# dental-unit-button_v1_0.net
KiCad netlist of a schematic drawn in Altium Designer
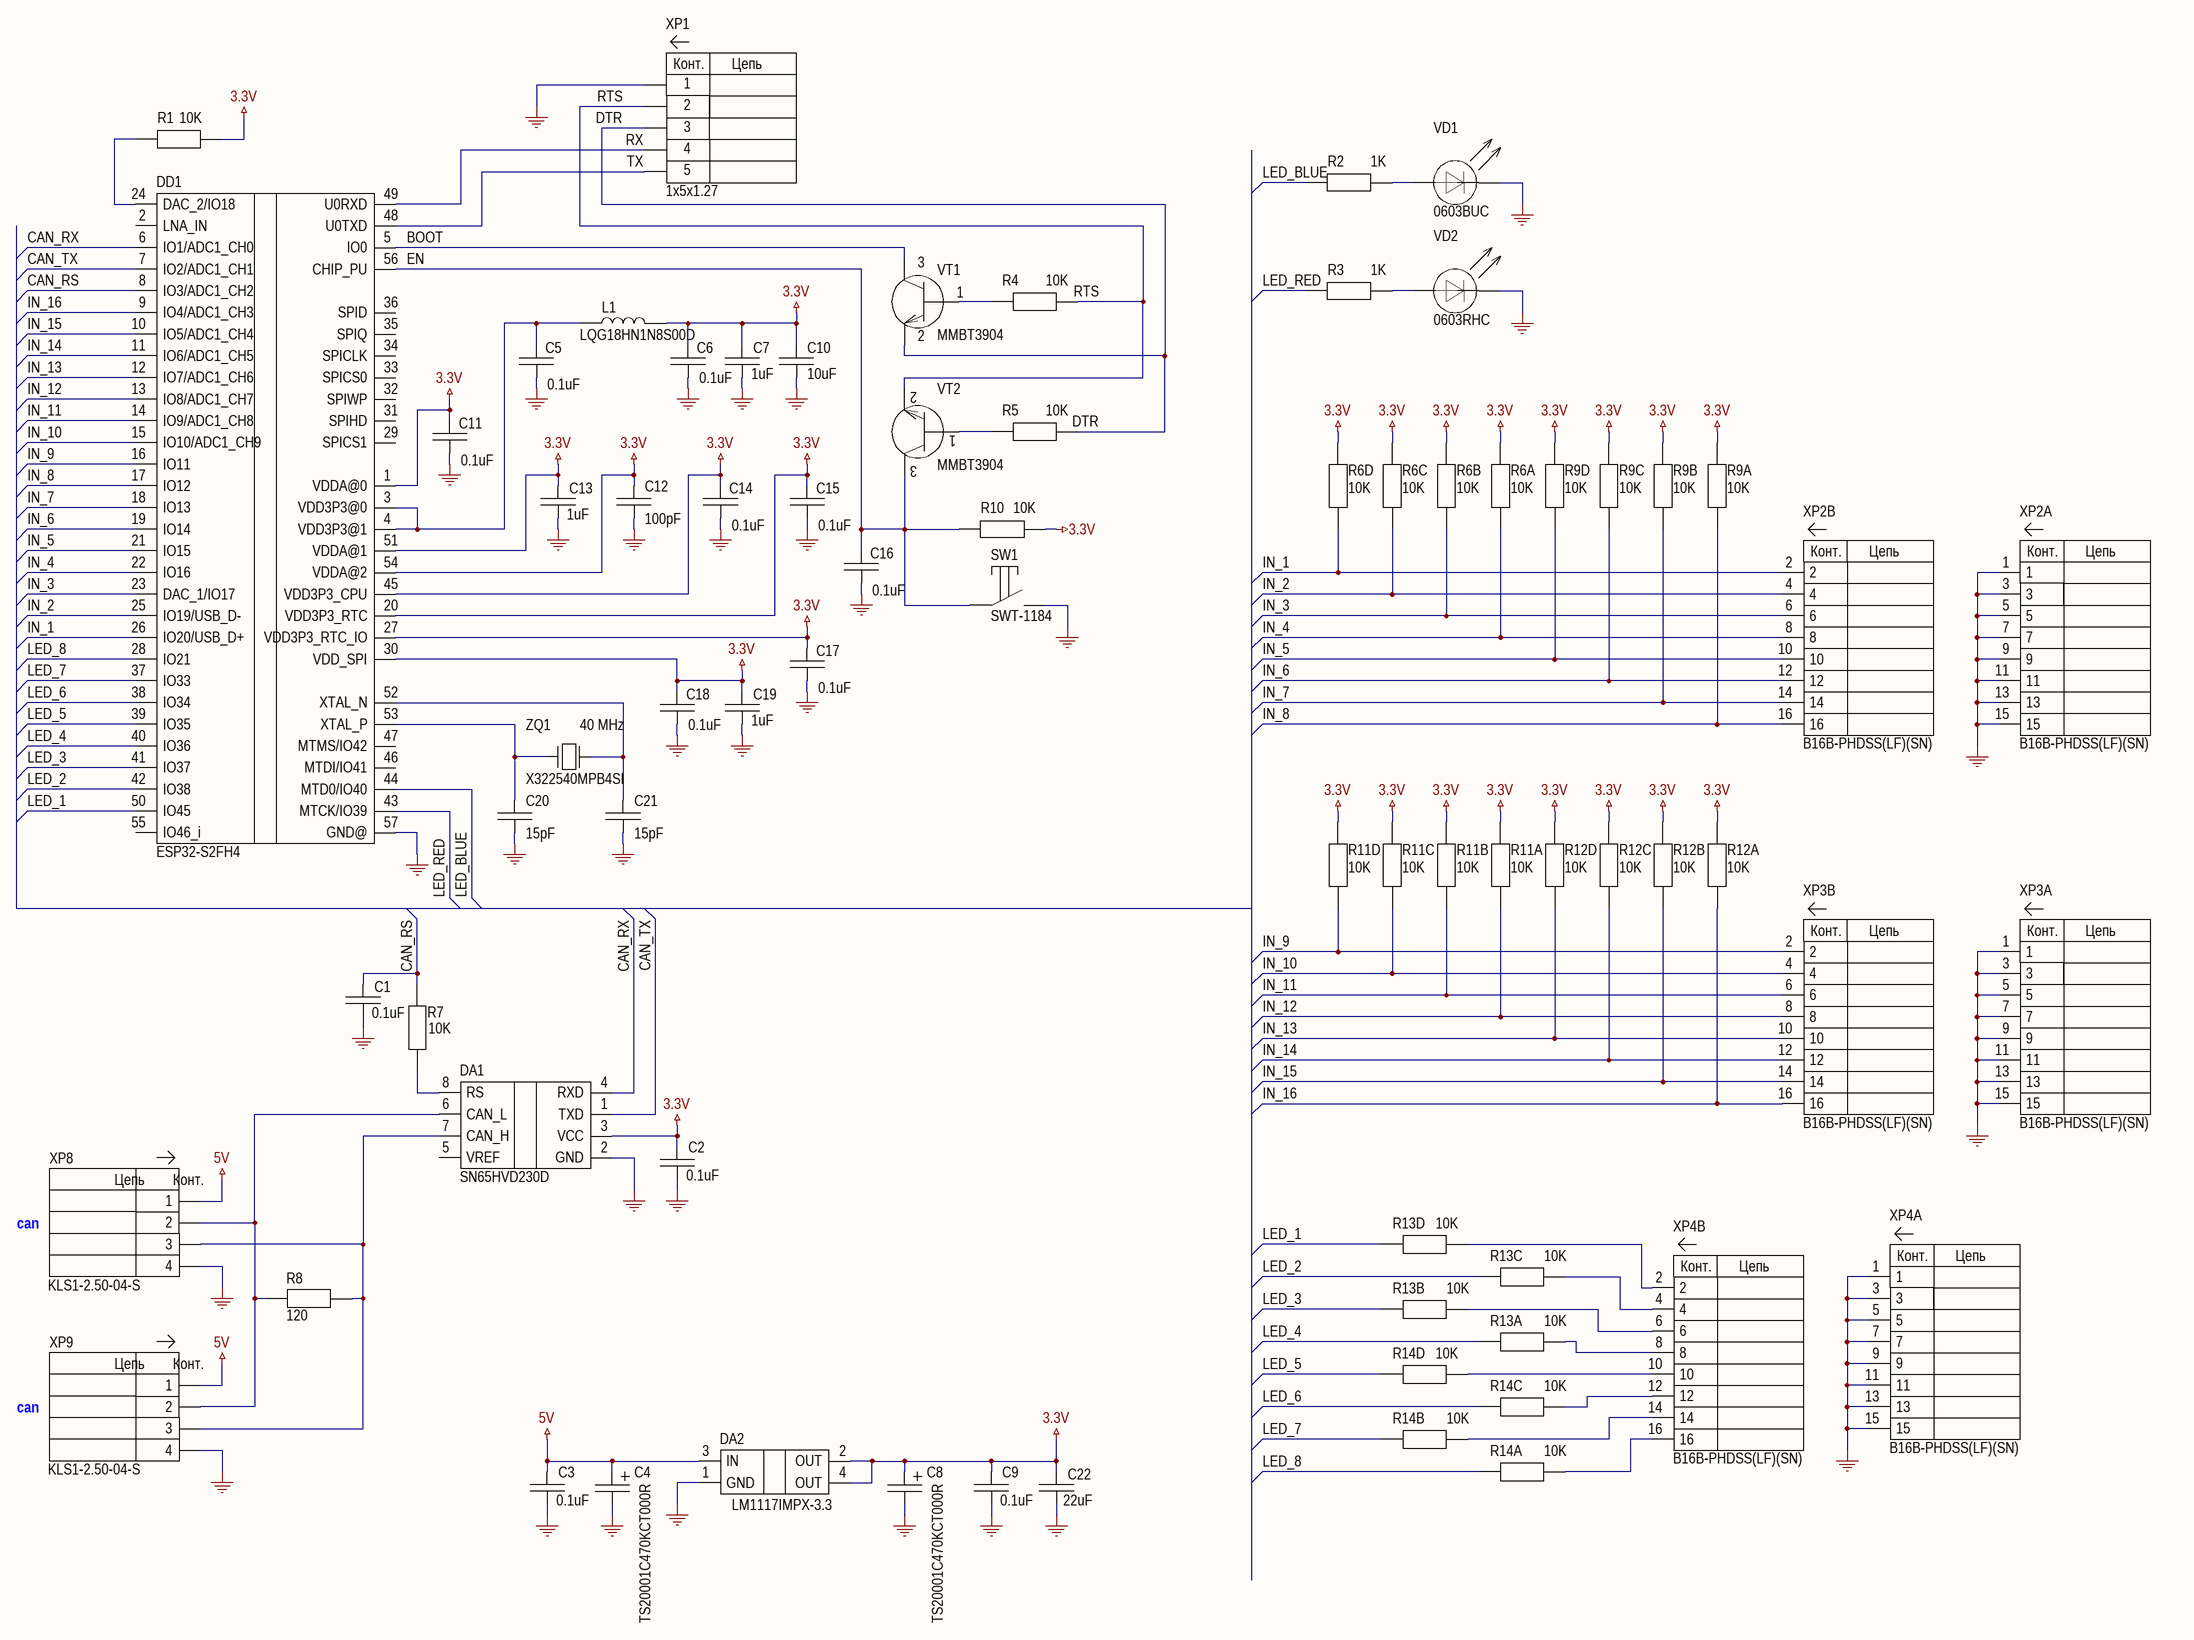
[diagram p0: dental-unit-button v1_0.SchDoc]

(export (version "E")
  (design (tool "Eeschema 10.0.6"))
  (components
    (comp (ref "C1")
      (value "0.1uF")
      (footprint "CC_0603")
      (description "Cap Ceramic, 0603, 0.1u, 10%, 16V, X7R (Yageo)")
      (fields (field (name "Comment") "CC0603KRX7R5BB104"))
      (libsource (lib "my_discrete_new") (part "C"))
    )
    (comp (ref "C2")
      (value "0.1uF")
      (footprint "CC_0603")
      (description "Cap Ceramic, 0603, 0.1u, 10%, 16V, X7R (Yageo)")
      (fields (field (name "Comment") "CC0603KRX7R5BB104"))
      (libsource (lib "my_discrete_new") (part "C"))
    )
    (comp (ref "C3")
      (value "0.1uF")
      (footprint "CC_0603")
      (description "Cap Ceramic, 0603, 0.1u, 10%, 16V, X7R (Yageo)")
      (fields (field (name "Comment") "CC0603KRX7R5BB104"))
      (libsource (lib "my_discrete_new") (part "C"))
    )
    (comp (ref "C4")
      (value "TS20001C470KCT000R")
      (footprint "CC_TANT_C")
      (description "47uF, 16v, C, 10%, @SUNTAN,")
      (libsource (lib "my_discrete_new") (part "C_polar"))
    )
    (comp (ref "C5")
      (value "0.1uF")
      (footprint "CC_0603")
      (description "Cap Ceramic, 0603, 0.1u, 10%, 16V, X7R (Yageo)")
      (fields (field (name "Comment") "CC0603KRX7R5BB104"))
      (libsource (lib "my_discrete_new") (part "C"))
    )
    (comp (ref "C6")
      (value "0.1uF")
      (footprint "CC_0603")
      (description "Cap Ceramic, 0603, 0.1u, 10%, 16V, X7R (Yageo)")
      (fields (field (name "Comment") "CC0603KRX7R5BB104"))
      (libsource (lib "my_discrete_new") (part "C"))
    )
    (comp (ref "C7")
      (value "1uF")
      (footprint "CC_0603")
      (description "Cap Ceramic, 0603, 1u, 10%, 50V, X5R (Sumsung)")
      (fields (field (name "Comment") "CL10A105KB8NNNC"))
      (libsource (lib "my_discrete_new") (part "C"))
    )
    (comp (ref "C8")
      (value "TS20001C470KCT000R")
      (footprint "CC_TANT_C")
      (description "47uF, 16v, C, 10%, @SUNTAN,")
      (libsource (lib "my_discrete_new") (part "C_polar"))
    )
    (comp (ref "C9")
      (value "0.1uF")
      (footprint "CC_0603")
      (description "Cap Ceramic, 0603, 0.1u, 10%, 16V, X7R (Yageo)")
      (fields (field (name "Comment") "CC0603KRX7R5BB104"))
      (libsource (lib "my_discrete_new") (part "C"))
    )
    (comp (ref "C10")
      (value "10uF")
      (footprint "CC_0603")
      (description "Cap Ceramic, 0603, 10u, 10%, 16V, X5R (Sumsung)")
      (fields (field (name "Comment") "CL10A106KP8NNNC"))
      (libsource (lib "my_discrete_new") (part "C"))
    )
    (comp (ref "C11")
      (value "0.1uF")
      (footprint "CC_0603")
      (description "Cap Ceramic, 0603, 0.1u, 10%, 16V, X7R (Yageo)")
      (fields (field (name "Comment") "CC0603KRX7R5BB104"))
      (libsource (lib "my_discrete_new") (part "C"))
    )
    (comp (ref "C12")
      (value "100pF")
      (footprint "CC_0603")
      (description "Cap Ceramic, 0603, 100p, 1%, 50V, NP0 (Yageo)")
      (fields (field (name "Comment") "CC0603FRNPO9BN101"))
      (libsource (lib "my_discrete_new") (part "C"))
    )
    (comp (ref "C13")
      (value "1uF")
      (footprint "CC_0603")
      (description "Cap Ceramic, 0603, 1u, 10%, 50V, X5R (Sumsung)")
      (fields (field (name "Comment") "CL10A105KB8NNNC"))
      (libsource (lib "my_discrete_new") (part "C"))
    )
    (comp (ref "C14")
      (value "0.1uF")
      (footprint "CC_0603")
      (description "Cap Ceramic, 0603, 0.1u, 10%, 16V, X7R (Yageo)")
      (fields (field (name "Comment") "CC0603KRX7R5BB104"))
      (libsource (lib "my_discrete_new") (part "C"))
    )
    (comp (ref "C15")
      (value "0.1uF")
      (footprint "CC_0603")
      (description "Cap Ceramic, 0603, 0.1u, 10%, 16V, X7R (Yageo)")
      (fields (field (name "Comment") "CC0603KRX7R5BB104"))
      (libsource (lib "my_discrete_new") (part "C"))
    )
    (comp (ref "C16")
      (value "0.1uF")
      (footprint "CC_0603")
      (description "Cap Ceramic, 0603, 0.1u, 10%, 16V, X7R (Yageo)")
      (fields (field (name "Comment") "CC0603KRX7R5BB104"))
      (libsource (lib "my_discrete_new") (part "C"))
    )
    (comp (ref "C17")
      (value "0.1uF")
      (footprint "CC_0603")
      (description "Cap Ceramic, 0603, 0.1u, 10%, 16V, X7R (Yageo)")
      (fields (field (name "Comment") "CC0603KRX7R5BB104"))
      (libsource (lib "my_discrete_new") (part "C"))
    )
    (comp (ref "C18")
      (value "0.1uF")
      (footprint "CC_0603")
      (description "Cap Ceramic, 0603, 0.1u, 10%, 16V, X7R (Yageo)")
      (fields (field (name "Comment") "CC0603KRX7R5BB104"))
      (libsource (lib "my_discrete_new") (part "C"))
    )
    (comp (ref "C19")
      (value "1uF")
      (footprint "CC_0603")
      (description "Cap Ceramic, 0603, 1u, 10%, 50V, X5R (Sumsung)")
      (fields (field (name "Comment") "CL10A105KB8NNNC"))
      (libsource (lib "my_discrete_new") (part "C"))
    )
    (comp (ref "C20")
      (value "15pF")
      (footprint "CC_0603")
      (description "Cap Ceramic, 0603, 15pF, 50V, NP0 (Yageo)")
      (fields (field (name "Comment") "CC0603GPNPO9BN150"))
      (libsource (lib "my_discrete_new") (part "C"))
    )
    (comp (ref "C21")
      (value "15pF")
      (footprint "CC_0603")
      (description "Cap Ceramic, 0603, 15pF, 50V, NP0 (Yageo)")
      (fields (field (name "Comment") "CC0603GPNPO9BN150"))
      (libsource (lib "my_discrete_new") (part "C"))
    )
    (comp (ref "C22")
      (value "22uF")
      (footprint "CC_0805")
      (description "Cap Ceramic, 0805, 22u, 20%, 6.3V, X5R, -55 +85C (Murata)")
      (fields (field (name "Comment") "GRM21BR60J226ME39L"))
      (libsource (lib "my_discrete_new") (part "C"))
    )
    (comp (ref "DA1")
      (value "SN65HVD230D")
      (footprint "SOIC-8")
      (description "3.3-V CAN TRANSCEIVERS, @TI")
      (libsource (lib "my_microschems_new") (part "SN65HVD230D"))
    )
    (comp (ref "DA2")
      (value "LM1117IMPX-3.3")
      (footprint "SOT-223")
      (description "LDO, 3.3v, 0.8A, SOT-223, Texas Instruments")
      (libsource (lib "my_microschems_new") (part "LM1117IMPX-3.3"))
    )
    (comp (ref "DD1")
      (value "ESP32-S2FH4")
      (footprint "QFN40P700X700X90-57T400N")
      (description "SMD WI-FI IC, ESP32-S2FH4, SINGAL-C")
      (fields (field (name "MF") "Espressif Systems") (field (name "MP") "ESP32-S2"))
      (libsource (lib "my_microschems_new") (part "ESP32-S2"))
    )
    (comp (ref "L1")
      (value "LQG18HN1N8S00D")
      (footprint "IC_0603")
      (description "1.1A, 1.8nH,100mΩ, 0603, Inductors (SMD), @MURATA")
      (libsource (lib "my_discrete_new") (part "L"))
    )
    (comp (ref "R1")
      (value "10K")
      (footprint "RC_0603")
      (description "Res, 0603, 10K, 1%, 0.25W (ф. Yageo)")
      (fields (field (name "POWER") "0.25W") (field (name "Comment") "AC0603FR-0710KL"))
      (libsource (lib "my_discrete_new") (part "R"))
    )
    (comp (ref "R2")
      (value "1K")
      (footprint "RC_0603")
      (description "Res, 0603, 1K 1%, 0.25W (ф. Yageo)")
      (fields (field (name "POWER") "0.25W") (field (name "Comment") "AC0603FR-071KL"))
      (libsource (lib "my_discrete_new") (part "R"))
    )
    (comp (ref "R3")
      (value "1K")
      (footprint "RC_0603")
      (description "Res, 0603, 1K 1%, 0.25W (ф. Yageo)")
      (fields (field (name "POWER") "0.25W") (field (name "Comment") "AC0603FR-071KL"))
      (libsource (lib "my_discrete_new") (part "R"))
    )
    (comp (ref "R4")
      (value "10K")
      (footprint "RC_0603")
      (description "Res, 0603, 10K, 1%, 0.25W (ф. Yageo)")
      (fields (field (name "POWER") "0.25W") (field (name "Comment") "AC0603FR-0710KL"))
      (libsource (lib "my_discrete_new") (part "R"))
    )
    (comp (ref "R5")
      (value "10K")
      (footprint "RC_0603")
      (description "Res, 0603, 10K, 1%, 0.25W (ф. Yageo)")
      (fields (field (name "POWER") "0.25W") (field (name "Comment") "AC0603FR-0710KL"))
      (libsource (lib "my_discrete_new") (part "R"))
    )
    (comp (ref "R6")
      (value "10K")
      (footprint "RC_0603x4")
      (description "Res, 0603x4, 10K, 5%, 0.25W (ф. Yageo)")
      (fields (field (name "POWER") "0.25W") (field (name "Comment") "YC164-JR-0710KL"))
      (libsource (lib "my_discrete_new") (part "R_Array"))
    )
    (comp (ref "R7")
      (value "10K")
      (footprint "RC_0603")
      (description "Res, 0603, 10K, 1%, 0.25W (ф. Yageo)")
      (fields (field (name "POWER") "0.25W") (field (name "Comment") "AC0603FR-0710KL"))
      (libsource (lib "my_discrete_new") (part "R"))
    )
    (comp (ref "R8")
      (value "120")
      (footprint "RC_0603")
      (description "Res, 0603, 120, 1%, 0.25W (ф. Yageo)")
      (fields (field (name "POWER") "0.25W") (field (name "Comment") "RC0603FR-07120RL"))
      (libsource (lib "my_discrete_new") (part "R"))
    )
    (comp (ref "R9")
      (value "10K")
      (footprint "RC_0603x4")
      (description "Res, 0603x4, 10K, 5%, 0.25W (ф. Yageo)")
      (fields (field (name "POWER") "0.25W") (field (name "Comment") "YC164-JR-0710KL"))
      (libsource (lib "my_discrete_new") (part "R_Array"))
    )
    (comp (ref "R10")
      (value "10K")
      (footprint "RC_0603")
      (description "Res, 0603, 10K, 1%, 0.25W (ф. Yageo)")
      (fields (field (name "POWER") "0.25W") (field (name "Comment") "AC0603FR-0710KL"))
      (libsource (lib "my_discrete_new") (part "R"))
    )
    (comp (ref "R11")
      (value "10K")
      (footprint "RC_0603x4")
      (description "Res, 0603x4, 10K, 5%, 0.25W (ф. Yageo)")
      (fields (field (name "POWER") "0.25W") (field (name "Comment") "YC164-JR-0710KL"))
      (libsource (lib "my_discrete_new") (part "R_Array"))
    )
    (comp (ref "R12")
      (value "10K")
      (footprint "RC_0603x4")
      (description "Res, 0603x4, 10K, 5%, 0.25W (ф. Yageo)")
      (fields (field (name "POWER") "0.25W") (field (name "Comment") "YC164-JR-0710KL"))
      (libsource (lib "my_discrete_new") (part "R_Array"))
    )
    (comp (ref "R13")
      (value "10K")
      (footprint "RC_0603x4")
      (description "Res, 0603x4, 10K, 5%, 0.25W (ф. Yageo)")
      (fields (field (name "POWER") "0.25W") (field (name "Comment") "YC164-JR-0710KL"))
      (libsource (lib "my_discrete_new") (part "R_Array"))
    )
    (comp (ref "R14")
      (value "10K")
      (footprint "RC_0603x4")
      (description "Res, 0603x4, 10K, 5%, 0.25W (ф. Yageo)")
      (fields (field (name "POWER") "0.25W") (field (name "Comment") "YC164-JR-0710KL"))
      (libsource (lib "my_discrete_new") (part "R_Array"))
    )
    (comp (ref "SW1")
      (value "SWT-1184")
      (footprint "IT-1184")
      (libsource (lib "my_discrete_new") (part "smd-side-push-button"))
    )
    (comp (ref "VD1")
      (value "0603BUC")
      (footprint "LED_0603")
      (description "Led, 0603, BLUE, 20mA, 125, 140MCD, CPMELEC")
      (libsource (lib "my_discrete_new") (part "LED"))
    )
    (comp (ref "VD2")
      (value "0603RHC")
      (footprint "LED_0603")
      (description "Led, 0603, RED, 20mA, 125, 140MCD, CPMELEC")
      (libsource (lib "my_discrete_new") (part "LED"))
    )
    (comp (ref "VT1")
      (value "MMBT3904")
      (footprint "SOT-23-3")
      (libsource (lib "my_microschems_new") (part "N-P-N-SOT-23"))
    )
    (comp (ref "VT2")
      (value "MMBT3904")
      (footprint "SOT-23-3")
      (libsource (lib "my_microschems_new") (part "N-P-N-SOT-23"))
    )
    (comp (ref "XP1")
      (value "1x5x1.27")
      (footprint "XT_1x5x1.27_offset")
      (libsource (lib "my_connectors_new") (part "XT_1x5x1_27"))
    )
    (comp (ref "XP2")
      (value "B16B-PHDSS(LF)(SN)")
      (footprint "B16B-PHDSS")
      (libsource (lib "my_connectors_new") (part "B16B-PHDSS(LF)(SN)"))
    )
    (comp (ref "XP3")
      (value "B16B-PHDSS(LF)(SN)")
      (footprint "B16B-PHDSS")
      (libsource (lib "my_connectors_new") (part "B16B-PHDSS(LF)(SN)"))
    )
    (comp (ref "XP4")
      (value "B16B-PHDSS(LF)(SN)")
      (footprint "B16B-PHDSS")
      (libsource (lib "my_connectors_new") (part "B16B-PHDSS(LF)(SN)"))
    )
    (comp (ref "XP8")
      (value "KLS1-2.50-04-S")
      (footprint "KLS1-2.50-04-S")
      (description "2.5mm, 4pin, KLS")
      (fields (field (name "NAME") "can"))
      (libsource (lib "my_connectors_new") (part "KLS1-2.50-04-x"))
    )
    (comp (ref "XP9")
      (value "KLS1-2.50-04-S")
      (footprint "KLS1-2.50-04-S")
      (description "2.5mm, 4pin, KLS")
      (fields (field (name "NAME") "can"))
      (libsource (lib "my_connectors_new") (part "KLS1-2.50-04-x"))
    )
    (comp (ref "ZQ1")
      (value "X322540MPB4SI")
      (footprint "OSC: 3225")
      (description "40MHz, 15pF, ±10ppm, SMD3225-4P, Crystals ROHS, @YXC")
      (fields (field (name "ALTIUM_VALUE") "40 MHz"))
      (libsource (lib "my_discrete_new") (part "OSC 3225"))
    )
  )
  (nets
    (net (code "1") (name "/BOOT") (class "Default")
      (node (ref "DD1") (pin "5") (pinfunction "IO0_5") (pintype "passive"))
      (node (ref "VT1") (pin "3") (pinfunction "C_3") (pintype "passive"))
    )
    (net (code "2") (name "/CAN_RS") (class "Default")
      (node (ref "C1") (pin "2") (pinfunction "2_2") (pintype "passive"))
      (node (ref "DD1") (pin "8") (pinfunction "IO3/ADC1_CH2_8") (pintype "passive"))
      (node (ref "R7") (pin "2") (pinfunction "2_2") (pintype "passive"))
    )
    (net (code "3") (name "/CAN_RX") (class "Default")
      (node (ref "DA1") (pin "4") (pinfunction "RXD_4") (pintype "power_in"))
      (node (ref "DD1") (pin "6") (pinfunction "IO1/ADC1_CH0_6") (pintype "passive"))
    )
    (net (code "4") (name "/CAN_TX") (class "Default")
      (node (ref "DA1") (pin "1") (pinfunction "TXD_1") (pintype "passive"))
      (node (ref "DD1") (pin "7") (pinfunction "IO2/ADC1_CH1_7") (pintype "passive"))
    )
    (net (code "5") (name "/DTR") (class "Default")
      (node (ref "R5") (pin "2") (pinfunction "2_2") (pintype "passive"))
      (node (ref "VT1") (pin "2") (pinfunction "E_2") (pintype "passive"))
      (node (ref "XP1") (pin "3") (pinfunction "3_3") (pintype "passive"))
    )
    (net (code "6") (name "/EN") (class "Default")
      (node (ref "C16") (pin "2") (pinfunction "2_2") (pintype "passive"))
      (node (ref "DD1") (pin "56") (pinfunction "CHIP_PU_56") (pintype "passive"))
      (node (ref "R10") (pin "1") (pinfunction "1_1") (pintype "passive"))
      (node (ref "SW1") (pin "1") (pinfunction "1_1") (pintype "passive"))
      (node (ref "VT2") (pin "3") (pinfunction "C_3") (pintype "passive"))
    )
    (net (code "7") (name "/IN_1") (class "Default")
      (node (ref "DD1") (pin "26") (pinfunction "IO20/USB_D+_26") (pintype "passive"))
      (node (ref "R6") (pin "4") (pinfunction "4_4") (pintype "passive"))
      (node (ref "XP2") (pin "2") (pinfunction "2_2") (pintype "passive"))
    )
    (net (code "8") (name "/IN_2") (class "Default")
      (node (ref "DD1") (pin "25") (pinfunction "IO19/USB_D-_25") (pintype "passive"))
      (node (ref "R6") (pin "3") (pinfunction "3_3") (pintype "passive"))
      (node (ref "XP2") (pin "4") (pinfunction "4_4") (pintype "passive"))
    )
    (net (code "9") (name "/IN_3") (class "Default")
      (node (ref "DD1") (pin "23") (pinfunction "DAC_1/IO17_23") (pintype "passive"))
      (node (ref "R6") (pin "2") (pinfunction "2_2") (pintype "passive"))
      (node (ref "XP2") (pin "6") (pinfunction "6_6") (pintype "passive"))
    )
    (net (code "10") (name "/IN_4") (class "Default")
      (node (ref "DD1") (pin "22") (pinfunction "IO16_22") (pintype "passive"))
      (node (ref "R6") (pin "1") (pinfunction "1_1") (pintype "passive"))
      (node (ref "XP2") (pin "8") (pinfunction "8_8") (pintype "passive"))
    )
    (net (code "11") (name "/IN_5") (class "Default")
      (node (ref "DD1") (pin "21") (pinfunction "IO15_21") (pintype "passive"))
      (node (ref "R9") (pin "4") (pinfunction "4_4") (pintype "passive"))
      (node (ref "XP2") (pin "10") (pinfunction "10_10") (pintype "passive"))
    )
    (net (code "12") (name "/IN_6") (class "Default")
      (node (ref "DD1") (pin "19") (pinfunction "IO14_19") (pintype "passive"))
      (node (ref "R9") (pin "3") (pinfunction "3_3") (pintype "passive"))
      (node (ref "XP2") (pin "12") (pinfunction "12_12") (pintype "passive"))
    )
    (net (code "13") (name "/IN_7") (class "Default")
      (node (ref "DD1") (pin "18") (pinfunction "IO13_18") (pintype "passive"))
      (node (ref "R9") (pin "2") (pinfunction "2_2") (pintype "passive"))
      (node (ref "XP2") (pin "14") (pinfunction "14_14") (pintype "passive"))
    )
    (net (code "14") (name "/IN_8") (class "Default")
      (node (ref "DD1") (pin "17") (pinfunction "IO12_17") (pintype "passive"))
      (node (ref "R9") (pin "1") (pinfunction "1_1") (pintype "passive"))
      (node (ref "XP2") (pin "16") (pinfunction "16_16") (pintype "passive"))
    )
    (net (code "15") (name "/IN_9") (class "Default")
      (node (ref "DD1") (pin "16") (pinfunction "IO11_16") (pintype "passive"))
      (node (ref "R11") (pin "4") (pinfunction "4_4") (pintype "passive"))
      (node (ref "XP3") (pin "2") (pinfunction "2_2") (pintype "passive"))
    )
    (net (code "16") (name "/IN_10") (class "Default")
      (node (ref "DD1") (pin "15") (pinfunction "IO10/ADC1_CH9_15") (pintype "passive"))
      (node (ref "R11") (pin "3") (pinfunction "3_3") (pintype "passive"))
      (node (ref "XP3") (pin "4") (pinfunction "4_4") (pintype "passive"))
    )
    (net (code "17") (name "/IN_11") (class "Default")
      (node (ref "DD1") (pin "14") (pinfunction "IO9/ADC1_CH8_14") (pintype "passive"))
      (node (ref "R11") (pin "2") (pinfunction "2_2") (pintype "passive"))
      (node (ref "XP3") (pin "6") (pinfunction "6_6") (pintype "passive"))
    )
    (net (code "18") (name "/IN_12") (class "Default")
      (node (ref "DD1") (pin "13") (pinfunction "IO8/ADC1_CH7_13") (pintype "passive"))
      (node (ref "R11") (pin "1") (pinfunction "1_1") (pintype "passive"))
      (node (ref "XP3") (pin "8") (pinfunction "8_8") (pintype "passive"))
    )
    (net (code "19") (name "/IN_13") (class "Default")
      (node (ref "DD1") (pin "12") (pinfunction "IO7/ADC1_CH6_12") (pintype "passive"))
      (node (ref "R12") (pin "4") (pinfunction "4_4") (pintype "passive"))
      (node (ref "XP3") (pin "10") (pinfunction "10_10") (pintype "passive"))
    )
    (net (code "20") (name "/IN_14") (class "Default")
      (node (ref "DD1") (pin "11") (pinfunction "IO6/ADC1_CH5_11") (pintype "passive"))
      (node (ref "R12") (pin "3") (pinfunction "3_3") (pintype "passive"))
      (node (ref "XP3") (pin "12") (pinfunction "12_12") (pintype "passive"))
    )
    (net (code "21") (name "/IN_15") (class "Default")
      (node (ref "DD1") (pin "10") (pinfunction "IO5/ADC1_CH4_10") (pintype "passive"))
      (node (ref "R12") (pin "2") (pinfunction "2_2") (pintype "passive"))
      (node (ref "XP3") (pin "14") (pinfunction "14_14") (pintype "passive"))
    )
    (net (code "22") (name "/IN_16") (class "Default")
      (node (ref "DD1") (pin "9") (pinfunction "IO4/ADC1_CH3_9") (pintype "passive"))
      (node (ref "R12") (pin "1") (pinfunction "1_1") (pintype "passive"))
      (node (ref "XP3") (pin "16") (pinfunction "16_16") (pintype "passive"))
    )
    (net (code "23") (name "/LED_1") (class "Default")
      (node (ref "DD1") (pin "50") (pinfunction "IO45_50") (pintype "passive"))
      (node (ref "R13") (pin "5") (pinfunction "5_5") (pintype "passive"))
    )
    (net (code "24") (name "/LED_2") (class "Default")
      (node (ref "DD1") (pin "42") (pinfunction "IO38_42") (pintype "passive"))
      (node (ref "R13") (pin "6") (pinfunction "6_6") (pintype "passive"))
    )
    (net (code "25") (name "/LED_3") (class "Default")
      (node (ref "DD1") (pin "41") (pinfunction "IO37_41") (pintype "passive"))
      (node (ref "R13") (pin "7") (pinfunction "7_7") (pintype "passive"))
    )
    (net (code "26") (name "/LED_4") (class "Default")
      (node (ref "DD1") (pin "40") (pinfunction "IO36_40") (pintype "passive"))
      (node (ref "R13") (pin "8") (pinfunction "8_8") (pintype "passive"))
    )
    (net (code "27") (name "/LED_5") (class "Default")
      (node (ref "DD1") (pin "39") (pinfunction "IO35_39") (pintype "passive"))
      (node (ref "R14") (pin "5") (pinfunction "5_5") (pintype "passive"))
    )
    (net (code "28") (name "/LED_6") (class "Default")
      (node (ref "DD1") (pin "38") (pinfunction "IO34_38") (pintype "passive"))
      (node (ref "R14") (pin "6") (pinfunction "6_6") (pintype "passive"))
    )
    (net (code "29") (name "/LED_7") (class "Default")
      (node (ref "DD1") (pin "37") (pinfunction "IO33_37") (pintype "passive"))
      (node (ref "R14") (pin "7") (pinfunction "7_7") (pintype "passive"))
    )
    (net (code "30") (name "/LED_8") (class "Default")
      (node (ref "DD1") (pin "28") (pinfunction "IO21_28") (pintype "passive"))
      (node (ref "R14") (pin "8") (pinfunction "8_8") (pintype "passive"))
    )
    (net (code "31") (name "/LED_BLUE") (class "Default")
      (node (ref "DD1") (pin "44") (pinfunction "MTD0/IO40_44") (pintype "passive"))
      (node (ref "R2") (pin "1") (pinfunction "1_1") (pintype "passive"))
    )
    (net (code "32") (name "/LED_RED") (class "Default")
      (node (ref "DD1") (pin "43") (pinfunction "MTCK/IO39_43") (pintype "passive"))
      (node (ref "R3") (pin "1") (pinfunction "1_1") (pintype "passive"))
    )
    (net (code "33") (name "/RTS") (class "Default")
      (node (ref "R4") (pin "2") (pinfunction "2_2") (pintype "passive"))
      (node (ref "VT2") (pin "2") (pinfunction "E_2") (pintype "passive"))
      (node (ref "XP1") (pin "2") (pinfunction "2_2") (pintype "passive"))
    )
    (net (code "34") (name "/RX") (class "Default")
      (node (ref "DD1") (pin "49") (pinfunction "U0RXD_49") (pintype "passive"))
      (node (ref "XP1") (pin "4") (pinfunction "4_4") (pintype "passive"))
    )
    (net (code "35") (name "/TX") (class "Default")
      (node (ref "DD1") (pin "48") (pinfunction "U0TXD_48") (pintype "passive"))
      (node (ref "XP1") (pin "5") (pinfunction "5_5") (pintype "passive"))
    )
    (net (code "36") (name "3.3V") (class "Default")
      (node (ref "C10") (pin "2") (pinfunction "2_2") (pintype "passive"))
      (node (ref "C11") (pin "2") (pinfunction "2_2") (pintype "passive"))
      (node (ref "C12") (pin "2") (pinfunction "2_2") (pintype "passive"))
      (node (ref "C13") (pin "2") (pinfunction "2_2") (pintype "passive"))
      (node (ref "C14") (pin "2") (pinfunction "2_2") (pintype "passive"))
      (node (ref "C15") (pin "2") (pinfunction "2_2") (pintype "passive"))
      (node (ref "C17") (pin "2") (pinfunction "2_2") (pintype "passive"))
      (node (ref "C18") (pin "2") (pinfunction "2_2") (pintype "passive"))
      (node (ref "C19") (pin "2") (pinfunction "2_2") (pintype "passive"))
      (node (ref "C2") (pin "2") (pinfunction "2_2") (pintype "passive"))
      (node (ref "C22") (pin "2") (pinfunction "2_2") (pintype "passive"))
      (node (ref "C6") (pin "2") (pinfunction "2_2") (pintype "passive"))
      (node (ref "C7") (pin "2") (pinfunction "2_2") (pintype "passive"))
      (node (ref "C8") (pin "1") (pinfunction "1_1") (pintype "passive"))
      (node (ref "C9") (pin "2") (pinfunction "2_2") (pintype "passive"))
      (node (ref "DA1") (pin "3") (pinfunction "VCC_3") (pintype "passive"))
      (node (ref "DA2") (pin "2") (pinfunction "OUT_2") (pintype "power_in"))
      (node (ref "DA2") (pin "4") (pinfunction "OUT_4") (pintype "power_in"))
      (node (ref "DD1") (pin "1") (pinfunction "VDDA@0_1") (pintype "passive"))
      (node (ref "DD1") (pin "20") (pinfunction "VDD3P3_RTC_20") (pintype "passive"))
      (node (ref "DD1") (pin "27") (pinfunction "VDD3P3_RTC_IO_27") (pintype "passive"))
      (node (ref "DD1") (pin "30") (pinfunction "VDD_SPI_30") (pintype "passive"))
      (node (ref "DD1") (pin "45") (pinfunction "VDD3P3_CPU_45") (pintype "passive"))
      (node (ref "DD1") (pin "51") (pinfunction "VDDA@1_51") (pintype "passive"))
      (node (ref "DD1") (pin "54") (pinfunction "VDDA@2_54") (pintype "passive"))
      (node (ref "L1") (pin "2") (pinfunction "2_2") (pintype "passive"))
      (node (ref "R1") (pin "2") (pinfunction "2_2") (pintype "passive"))
      (node (ref "R10") (pin "2") (pinfunction "2_2") (pintype "passive"))
      (node (ref "R11") (pin "5") (pinfunction "5_5") (pintype "passive"))
      (node (ref "R11") (pin "6") (pinfunction "6_6") (pintype "passive"))
      (node (ref "R11") (pin "7") (pinfunction "7_7") (pintype "passive"))
      (node (ref "R11") (pin "8") (pinfunction "8_8") (pintype "passive"))
      (node (ref "R12") (pin "5") (pinfunction "5_5") (pintype "passive"))
      (node (ref "R12") (pin "6") (pinfunction "6_6") (pintype "passive"))
      (node (ref "R12") (pin "7") (pinfunction "7_7") (pintype "passive"))
      (node (ref "R12") (pin "8") (pinfunction "8_8") (pintype "passive"))
      (node (ref "R6") (pin "5") (pinfunction "5_5") (pintype "passive"))
      (node (ref "R6") (pin "6") (pinfunction "6_6") (pintype "passive"))
      (node (ref "R6") (pin "7") (pinfunction "7_7") (pintype "passive"))
      (node (ref "R6") (pin "8") (pinfunction "8_8") (pintype "passive"))
      (node (ref "R9") (pin "5") (pinfunction "5_5") (pintype "passive"))
      (node (ref "R9") (pin "6") (pinfunction "6_6") (pintype "passive"))
      (node (ref "R9") (pin "7") (pinfunction "7_7") (pintype "passive"))
      (node (ref "R9") (pin "8") (pinfunction "8_8") (pintype "passive"))
    )
    (net (code "37") (name "5V") (class "Default")
      (node (ref "C3") (pin "2") (pinfunction "2_2") (pintype "passive"))
      (node (ref "C4") (pin "1") (pinfunction "1_1") (pintype "passive"))
      (node (ref "DA2") (pin "3") (pinfunction "IN_3") (pintype "passive"))
      (node (ref "XP8") (pin "1") (pinfunction "1_1") (pintype "passive"))
      (node (ref "XP9") (pin "1") (pinfunction "1_1") (pintype "passive"))
    )
    (net (code "38") (name "GND") (class "Default")
      (node (ref "C1") (pin "1") (pinfunction "1_1") (pintype "passive"))
      (node (ref "C10") (pin "1") (pinfunction "1_1") (pintype "passive"))
      (node (ref "C11") (pin "1") (pinfunction "1_1") (pintype "passive"))
      (node (ref "C12") (pin "1") (pinfunction "1_1") (pintype "passive"))
      (node (ref "C13") (pin "1") (pinfunction "1_1") (pintype "passive"))
      (node (ref "C14") (pin "1") (pinfunction "1_1") (pintype "passive"))
      (node (ref "C15") (pin "1") (pinfunction "1_1") (pintype "passive"))
      (node (ref "C16") (pin "1") (pinfunction "1_1") (pintype "passive"))
      (node (ref "C17") (pin "1") (pinfunction "1_1") (pintype "passive"))
      (node (ref "C18") (pin "1") (pinfunction "1_1") (pintype "passive"))
      (node (ref "C19") (pin "1") (pinfunction "1_1") (pintype "passive"))
      (node (ref "C2") (pin "1") (pinfunction "1_1") (pintype "passive"))
      (node (ref "C20") (pin "1") (pinfunction "1_1") (pintype "passive"))
      (node (ref "C21") (pin "1") (pinfunction "1_1") (pintype "passive"))
      (node (ref "C22") (pin "1") (pinfunction "1_1") (pintype "passive"))
      (node (ref "C3") (pin "1") (pinfunction "1_1") (pintype "passive"))
      (node (ref "C4") (pin "2") (pinfunction "2_2") (pintype "passive"))
      (node (ref "C5") (pin "1") (pinfunction "1_1") (pintype "passive"))
      (node (ref "C6") (pin "1") (pinfunction "1_1") (pintype "passive"))
      (node (ref "C7") (pin "1") (pinfunction "1_1") (pintype "passive"))
      (node (ref "C8") (pin "2") (pinfunction "2_2") (pintype "passive"))
      (node (ref "C9") (pin "1") (pinfunction "1_1") (pintype "passive"))
      (node (ref "DA1") (pin "2") (pinfunction "GND_2") (pintype "passive"))
      (node (ref "DA2") (pin "1") (pinfunction "GND_1") (pintype "passive"))
      (node (ref "DD1") (pin "57") (pinfunction "GND@_57") (pintype "passive"))
      (node (ref "SW1") (pin "2") (pinfunction "2_2") (pintype "passive"))
      (node (ref "VD1") (pin "2") (pinfunction "C_2") (pintype "passive"))
      (node (ref "VD2") (pin "2") (pinfunction "C_2") (pintype "passive"))
      (node (ref "XP1") (pin "1") (pinfunction "1_1") (pintype "passive"))
      (node (ref "XP2") (pin "1") (pinfunction "1_1") (pintype "passive"))
      (node (ref "XP2") (pin "11") (pinfunction "11_11") (pintype "passive"))
      (node (ref "XP2") (pin "13") (pinfunction "13_13") (pintype "passive"))
      (node (ref "XP2") (pin "15") (pinfunction "15_15") (pintype "passive"))
      (node (ref "XP2") (pin "3") (pinfunction "3_3") (pintype "passive"))
      (node (ref "XP2") (pin "5") (pinfunction "5_5") (pintype "passive"))
      (node (ref "XP2") (pin "7") (pinfunction "7_7") (pintype "passive"))
      (node (ref "XP2") (pin "9") (pinfunction "9_9") (pintype "passive"))
      (node (ref "XP3") (pin "1") (pinfunction "1_1") (pintype "passive"))
      (node (ref "XP3") (pin "11") (pinfunction "11_11") (pintype "passive"))
      (node (ref "XP3") (pin "13") (pinfunction "13_13") (pintype "passive"))
      (node (ref "XP3") (pin "15") (pinfunction "15_15") (pintype "passive"))
      (node (ref "XP3") (pin "3") (pinfunction "3_3") (pintype "passive"))
      (node (ref "XP3") (pin "5") (pinfunction "5_5") (pintype "passive"))
      (node (ref "XP3") (pin "7") (pinfunction "7_7") (pintype "passive"))
      (node (ref "XP3") (pin "9") (pinfunction "9_9") (pintype "passive"))
      (node (ref "XP4") (pin "1") (pinfunction "1_1") (pintype "passive"))
      (node (ref "XP4") (pin "11") (pinfunction "11_11") (pintype "passive"))
      (node (ref "XP4") (pin "13") (pinfunction "13_13") (pintype "passive"))
      (node (ref "XP4") (pin "15") (pinfunction "15_15") (pintype "passive"))
      (node (ref "XP4") (pin "3") (pinfunction "3_3") (pintype "passive"))
      (node (ref "XP4") (pin "5") (pinfunction "5_5") (pintype "passive"))
      (node (ref "XP4") (pin "7") (pinfunction "7_7") (pintype "passive"))
      (node (ref "XP4") (pin "9") (pinfunction "9_9") (pintype "passive"))
      (node (ref "XP8") (pin "4") (pinfunction "4_4") (pintype "passive"))
      (node (ref "XP9") (pin "4") (pinfunction "4_4") (pintype "passive"))
    )
    (net (code "39") (name "Net-(DA1-CAN_H)") (class "Default")
      (node (ref "DA1") (pin "7") (pinfunction "CAN_H_7") (pintype "passive"))
      (node (ref "R8") (pin "1") (pinfunction "1_1") (pintype "passive"))
      (node (ref "XP8") (pin "3") (pinfunction "3_3") (pintype "passive"))
      (node (ref "XP9") (pin "3") (pinfunction "3_3") (pintype "passive"))
    )
    (net (code "40") (name "Net-(DA1-CAN_L)") (class "Default")
      (node (ref "DA1") (pin "6") (pinfunction "CAN_L_6") (pintype "passive"))
      (node (ref "R8") (pin "2") (pinfunction "2_2") (pintype "passive"))
      (node (ref "XP8") (pin "2") (pinfunction "2_2") (pintype "passive"))
      (node (ref "XP9") (pin "2") (pinfunction "2_2") (pintype "passive"))
    )
    (net (code "41") (name "Net-(DA1-RS)") (class "Default")
      (node (ref "DA1") (pin "8") (pinfunction "RS_8") (pintype "power_in"))
      (node (ref "R7") (pin "1") (pinfunction "1_1") (pintype "passive"))
    )
    (net (code "42") (name "Net-(DD1-DAC_2{slash}IO18)") (class "Default")
      (node (ref "DD1") (pin "24") (pinfunction "DAC_2/IO18_24") (pintype "passive"))
      (node (ref "R1") (pin "1") (pinfunction "1_1") (pintype "passive"))
    )
    (net (code "43") (name "Net-(DD1-VDD3P3@0)") (class "Default")
      (node (ref "C5") (pin "2") (pinfunction "2_2") (pintype "passive"))
      (node (ref "DD1") (pin "3") (pinfunction "VDD3P3@0_3") (pintype "passive"))
      (node (ref "DD1") (pin "4") (pinfunction "VDD3P3@1_4") (pintype "passive"))
      (node (ref "L1") (pin "1") (pinfunction "1_1") (pintype "passive"))
    )
    (net (code "44") (name "Net-(DD1-XTAL_N)") (class "Default")
      (node (ref "C21") (pin "2") (pinfunction "2_2") (pintype "passive"))
      (node (ref "DD1") (pin "52") (pinfunction "XTAL_N_52") (pintype "passive"))
      (node (ref "ZQ1") (pin "3") (pinfunction "3_3") (pintype "passive"))
    )
    (net (code "45") (name "Net-(DD1-XTAL_P)") (class "Default")
      (node (ref "C20") (pin "2") (pinfunction "2_2") (pintype "passive"))
      (node (ref "DD1") (pin "53") (pinfunction "XTAL_P_53") (pintype "passive"))
      (node (ref "ZQ1") (pin "1") (pinfunction "1_1") (pintype "passive"))
    )
    (net (code "46") (name "Net-(R13-Pad1)") (class "Default")
      (node (ref "R13") (pin "1") (pinfunction "1_1") (pintype "passive"))
      (node (ref "XP4") (pin "8") (pinfunction "8_8") (pintype "passive"))
    )
    (net (code "47") (name "Net-(R13-Pad2)") (class "Default")
      (node (ref "R13") (pin "2") (pinfunction "2_2") (pintype "passive"))
      (node (ref "XP4") (pin "6") (pinfunction "6_6") (pintype "passive"))
    )
    (net (code "48") (name "Net-(R13-Pad3)") (class "Default")
      (node (ref "R13") (pin "3") (pinfunction "3_3") (pintype "passive"))
      (node (ref "XP4") (pin "4") (pinfunction "4_4") (pintype "passive"))
    )
    (net (code "49") (name "Net-(R13-Pad4)") (class "Default")
      (node (ref "R13") (pin "4") (pinfunction "4_4") (pintype "passive"))
      (node (ref "XP4") (pin "2") (pinfunction "2_2") (pintype "passive"))
    )
    (net (code "50") (name "Net-(R14-Pad1)") (class "Default")
      (node (ref "R14") (pin "1") (pinfunction "1_1") (pintype "passive"))
      (node (ref "XP4") (pin "16") (pinfunction "16_16") (pintype "passive"))
    )
    (net (code "51") (name "Net-(R14-Pad2)") (class "Default")
      (node (ref "R14") (pin "2") (pinfunction "2_2") (pintype "passive"))
      (node (ref "XP4") (pin "14") (pinfunction "14_14") (pintype "passive"))
    )
    (net (code "52") (name "Net-(R14-Pad3)") (class "Default")
      (node (ref "R14") (pin "3") (pinfunction "3_3") (pintype "passive"))
      (node (ref "XP4") (pin "12") (pinfunction "12_12") (pintype "passive"))
    )
    (net (code "53") (name "Net-(R14-Pad4)") (class "Default")
      (node (ref "R14") (pin "4") (pinfunction "4_4") (pintype "passive"))
      (node (ref "XP4") (pin "10") (pinfunction "10_10") (pintype "passive"))
    )
    (net (code "54") (name "Net-(VD1-A)") (class "Default")
      (node (ref "R2") (pin "2") (pinfunction "2_2") (pintype "passive"))
      (node (ref "VD1") (pin "1") (pinfunction "A_1") (pintype "passive"))
    )
    (net (code "55") (name "Net-(VD2-A)") (class "Default")
      (node (ref "R3") (pin "2") (pinfunction "2_2") (pintype "passive"))
      (node (ref "VD2") (pin "1") (pinfunction "A_1") (pintype "passive"))
    )
    (net (code "56") (name "Net-(VT1-B)") (class "Default")
      (node (ref "R4") (pin "1") (pinfunction "1_1") (pintype "passive"))
      (node (ref "VT1") (pin "1") (pinfunction "B_1") (pintype "passive"))
    )
    (net (code "57") (name "Net-(VT2-B)") (class "Default")
      (node (ref "R5") (pin "1") (pinfunction "1_1") (pintype "passive"))
      (node (ref "VT2") (pin "1") (pinfunction "B_1") (pintype "passive"))
    )
    (net (code "58") (name "unconnected-(DA1-VREF-Pad5)") (class "Default")
      (node (ref "DA1") (pin "5") (pinfunction "VREF_5") (pintype "passive"))
    )
    (net (code "59") (name "unconnected-(DD1-IO46_i-Pad55)") (class "Default")
      (node (ref "DD1") (pin "55") (pinfunction "IO46_i_55") (pintype "passive"))
    )
    (net (code "60") (name "unconnected-(DD1-LNA_IN-Pad2)") (class "Default")
      (node (ref "DD1") (pin "2") (pinfunction "LNA_IN_2") (pintype "passive"))
    )
    (net (code "61") (name "unconnected-(DD1-MTDI{slash}IO41-Pad46)") (class "Default")
      (node (ref "DD1") (pin "46") (pinfunction "MTDI/IO41_46") (pintype "passive"))
    )
    (net (code "62") (name "unconnected-(DD1-MTMS{slash}IO42-Pad47)") (class "Default")
      (node (ref "DD1") (pin "47") (pinfunction "MTMS/IO42_47") (pintype "passive"))
    )
    (net (code "63") (name "unconnected-(DD1-SPICLK-Pad34)") (class "Default")
      (node (ref "DD1") (pin "34") (pinfunction "SPICLK_34") (pintype "passive"))
    )
    (net (code "64") (name "unconnected-(DD1-SPICS0-Pad33)") (class "Default")
      (node (ref "DD1") (pin "33") (pinfunction "SPICS0_33") (pintype "passive"))
    )
    (net (code "65") (name "unconnected-(DD1-SPICS1-Pad29)") (class "Default")
      (node (ref "DD1") (pin "29") (pinfunction "SPICS1_29") (pintype "passive"))
    )
    (net (code "66") (name "unconnected-(DD1-SPID-Pad36)") (class "Default")
      (node (ref "DD1") (pin "36") (pinfunction "SPID_36") (pintype "passive"))
    )
    (net (code "67") (name "unconnected-(DD1-SPIHD-Pad31)") (class "Default")
      (node (ref "DD1") (pin "31") (pinfunction "SPIHD_31") (pintype "passive"))
    )
    (net (code "68") (name "unconnected-(DD1-SPIQ-Pad35)") (class "Default")
      (node (ref "DD1") (pin "35") (pinfunction "SPIQ_35") (pintype "passive"))
    )
    (net (code "69") (name "unconnected-(DD1-SPIWP-Pad32)") (class "Default")
      (node (ref "DD1") (pin "32") (pinfunction "SPIWP_32") (pintype "passive"))
    )
    (net (code "70") (name "unconnected-(ZQ1-Pad2)") (class "Default")
      (node (ref "ZQ1") (pin "2") (pinfunction "2_2") (pintype "passive"))
    )
    (net (code "71") (name "unconnected-(ZQ1-Pad4)") (class "Default")
      (node (ref "ZQ1") (pin "4") (pinfunction "4_4") (pintype "passive"))
    )
  )
)
